# MainBoardV1.net
KiCad netlist of a schematic drawn in EAGLE
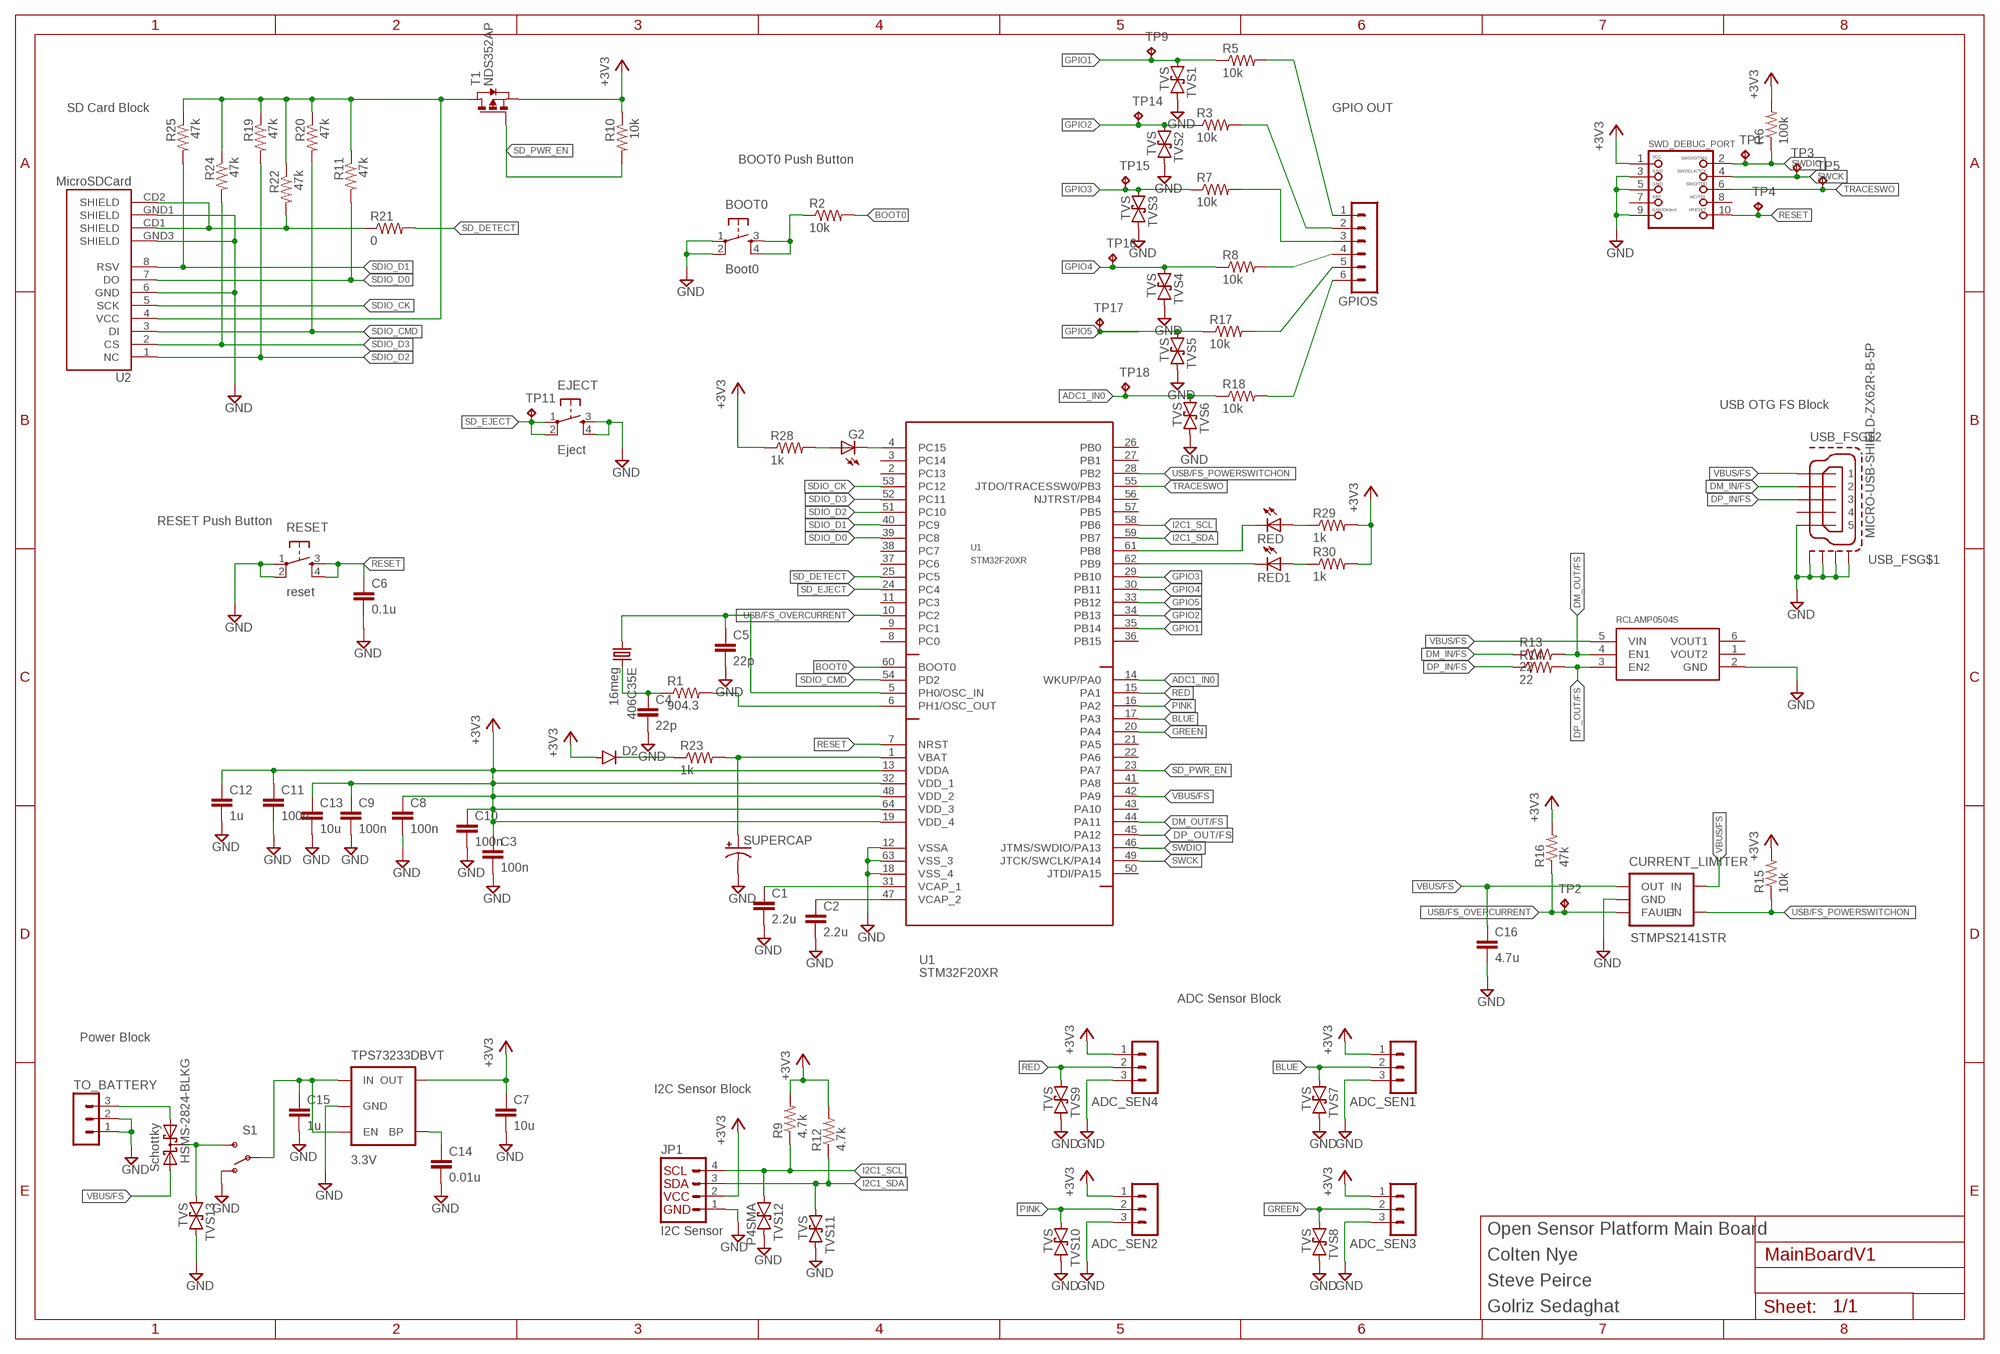
[diagram p0: schematic, sheet 1]

(export (version "E")
  (design (tool "Eeschema 10.0.6"))
  (components
    (comp (ref "406C35E")
      (value "16meg")
      (footprint "eagle-import:CTS406")
      (libsource (lib "eagle-import") (part "CRYSTALCTS406"))
    )
    (comp (ref "ADC_SEN1")
      (value "MA03-1")
      (footprint "eagle-import:MA03-1")
      (libsource (lib "eagle-import") (part "MA03-1"))
    )
    (comp (ref "ADC_SEN2")
      (value "MA03-1")
      (footprint "eagle-import:MA03-1")
      (libsource (lib "eagle-import") (part "MA03-1"))
    )
    (comp (ref "ADC_SEN3")
      (value "MA03-1")
      (footprint "eagle-import:MA03-1")
      (libsource (lib "eagle-import") (part "MA03-1"))
    )
    (comp (ref "ADC_SEN4")
      (value "MA03-1")
      (footprint "eagle-import:MA03-1")
      (libsource (lib "eagle-import") (part "MA03-1"))
    )
    (comp (ref "BOOT0")
      (value "Boot0")
      (footprint "eagle-import:TACTILE-SWITCH-SMD")
      (libsource (lib "eagle-import") (part "TAC_SWITCHSMD"))
    )
    (comp (ref "C1")
      (value "2.2u")
      (footprint "eagle-import:C0805")
      (libsource (lib "eagle-import") (part "C-EUC0805"))
    )
    (comp (ref "C2")
      (value "2.2u")
      (footprint "eagle-import:C0805")
      (libsource (lib "eagle-import") (part "C-EUC0805"))
    )
    (comp (ref "C3")
      (value "100n")
      (footprint "eagle-import:C0805")
      (libsource (lib "eagle-import") (part "C-EUC0805"))
    )
    (comp (ref "C4")
      (value "22p")
      (footprint "eagle-import:C0805")
      (libsource (lib "eagle-import") (part "C-EUC0805"))
    )
    (comp (ref "C5")
      (value "22p")
      (footprint "eagle-import:C0805")
      (libsource (lib "eagle-import") (part "C-EUC0805"))
    )
    (comp (ref "C6")
      (value "0.1u")
      (footprint "eagle-import:C0805")
      (libsource (lib "eagle-import") (part "C-EUC0805"))
    )
    (comp (ref "C7")
      (value "10u")
      (footprint "eagle-import:C0805")
      (libsource (lib "eagle-import") (part "C-EUC0805"))
    )
    (comp (ref "C8")
      (value "100n")
      (footprint "eagle-import:C0805")
      (libsource (lib "eagle-import") (part "C-EUC0805"))
    )
    (comp (ref "C9")
      (value "100n")
      (footprint "eagle-import:C0805")
      (libsource (lib "eagle-import") (part "C-EUC0805"))
    )
    (comp (ref "C10")
      (value "100n")
      (footprint "eagle-import:C0805")
      (libsource (lib "eagle-import") (part "C-EUC0805"))
    )
    (comp (ref "C11")
      (value "100n")
      (footprint "eagle-import:C0805")
      (libsource (lib "eagle-import") (part "C-EUC0805"))
    )
    (comp (ref "C12")
      (value "1u")
      (footprint "eagle-import:C0805")
      (libsource (lib "eagle-import") (part "C-EUC0805"))
    )
    (comp (ref "C13")
      (value "10u")
      (footprint "eagle-import:C0805")
      (libsource (lib "eagle-import") (part "C-EUC0805"))
    )
    (comp (ref "C14")
      (value "0.01u")
      (footprint "eagle-import:C0805")
      (libsource (lib "eagle-import") (part "C-EUC0805"))
    )
    (comp (ref "C15")
      (value "1u")
      (footprint "eagle-import:C0805")
      (libsource (lib "eagle-import") (part "C-EUC0805"))
    )
    (comp (ref "C16")
      (value "4.7u")
      (footprint "eagle-import:C0805")
      (libsource (lib "eagle-import") (part "C-EUC0805"))
    )
    (comp (ref "CURRENT_LIMITER")
      (value "STMPS2141STR")
      (footprint "eagle-import:SOT23-5")
      (libsource (lib "eagle-import") (part "V_REG_NCP1400SOT23-5"))
    )
    (comp (ref "D2")
      (value "DIODESMA")
      (footprint "eagle-import:SMA-DIODE")
      (libsource (lib "eagle-import") (part "DIODESMA"))
    )
    (comp (ref "EJECT")
      (value "Eject")
      (footprint "eagle-import:TACTILE-SWITCH-SMD")
      (libsource (lib "eagle-import") (part "TAC_SWITCHSMD"))
    )
    (comp (ref "G2")
      (value "LEDSML0805")
      (footprint "eagle-import:SML0805")
      (libsource (lib "eagle-import") (part "LEDSML0805"))
    )
    (comp (ref "GPIOS")
      (value "MA06-1")
      (footprint "eagle-import:MA06-1")
      (libsource (lib "eagle-import") (part "MA06-1"))
    )
    (comp (ref "HSMS-2824-BLKG")
      (value "Schottky")
      (footprint "eagle-import:SOT23")
      (libsource (lib "eagle-import") (part "BAS70-05"))
    )
    (comp (ref "JP1")
      (value "I2C Sensor")
      (footprint "eagle-import:1X04")
      (libsource (lib "eagle-import") (part "I2C_STANDARD"))
    )
    (comp (ref "R1")
      (value "904.3")
      (footprint "eagle-import:R0805")
      (libsource (lib "eagle-import") (part "R-US_R0805"))
    )
    (comp (ref "R2")
      (value "10k")
      (footprint "eagle-import:R0805")
      (libsource (lib "eagle-import") (part "R-US_R0805"))
    )
    (comp (ref "R3")
      (value "10k")
      (footprint "eagle-import:R0805")
      (libsource (lib "eagle-import") (part "R-US_R0805"))
    )
    (comp (ref "R5")
      (value "10k")
      (footprint "eagle-import:R0805")
      (libsource (lib "eagle-import") (part "R-US_R0805"))
    )
    (comp (ref "R6")
      (value "100k")
      (footprint "eagle-import:R0805")
      (libsource (lib "eagle-import") (part "R-US_R0805"))
    )
    (comp (ref "R7")
      (value "10k")
      (footprint "eagle-import:R0805")
      (libsource (lib "eagle-import") (part "R-US_R0805"))
    )
    (comp (ref "R8")
      (value "10k")
      (footprint "eagle-import:R0805")
      (libsource (lib "eagle-import") (part "R-US_R0805"))
    )
    (comp (ref "R9")
      (value "4.7k")
      (footprint "eagle-import:R0805")
      (libsource (lib "eagle-import") (part "R-US_R0805"))
    )
    (comp (ref "R10")
      (value "10k")
      (footprint "eagle-import:R0805")
      (libsource (lib "eagle-import") (part "R-US_R0805"))
    )
    (comp (ref "R11")
      (value "47k")
      (footprint "eagle-import:R0805")
      (libsource (lib "eagle-import") (part "R-US_R0805"))
    )
    (comp (ref "R12")
      (value "4.7k")
      (footprint "eagle-import:R0805")
      (libsource (lib "eagle-import") (part "R-US_R0805"))
    )
    (comp (ref "R13")
      (value "22")
      (footprint "eagle-import:R0805")
      (libsource (lib "eagle-import") (part "R-US_R0805"))
    )
    (comp (ref "R14")
      (value "22")
      (footprint "eagle-import:R0805")
      (libsource (lib "eagle-import") (part "R-US_R0805"))
    )
    (comp (ref "R15")
      (value "10k")
      (footprint "eagle-import:R0805")
      (libsource (lib "eagle-import") (part "R-US_R0805"))
    )
    (comp (ref "R16")
      (value "47k")
      (footprint "eagle-import:R0805")
      (libsource (lib "eagle-import") (part "R-US_R0805"))
    )
    (comp (ref "R17")
      (value "10k")
      (footprint "eagle-import:R0805")
      (libsource (lib "eagle-import") (part "R-US_R0805"))
    )
    (comp (ref "R18")
      (value "10k")
      (footprint "eagle-import:R0805")
      (libsource (lib "eagle-import") (part "R-US_R0805"))
    )
    (comp (ref "R19")
      (value "47k")
      (footprint "eagle-import:R0805")
      (libsource (lib "eagle-import") (part "R-US_R0805"))
    )
    (comp (ref "R20")
      (value "47k")
      (footprint "eagle-import:R0805")
      (libsource (lib "eagle-import") (part "R-US_R0805"))
    )
    (comp (ref "R21")
      (value "0")
      (footprint "eagle-import:R0805")
      (libsource (lib "eagle-import") (part "R-US_R0805"))
    )
    (comp (ref "R22")
      (value "47k")
      (footprint "eagle-import:R0805")
      (libsource (lib "eagle-import") (part "R-US_R0805"))
    )
    (comp (ref "R23")
      (value "1k")
      (footprint "eagle-import:R0805")
      (libsource (lib "eagle-import") (part "R-US_R0805"))
    )
    (comp (ref "R24")
      (value "47k")
      (footprint "eagle-import:R0805")
      (libsource (lib "eagle-import") (part "R-US_R0805"))
    )
    (comp (ref "R25")
      (value "47k")
      (footprint "eagle-import:R0805")
      (libsource (lib "eagle-import") (part "R-US_R0805"))
    )
    (comp (ref "R28")
      (value "1k")
      (footprint "eagle-import:R0805")
      (libsource (lib "eagle-import") (part "R-US_R0805"))
    )
    (comp (ref "R29")
      (value "1k")
      (footprint "eagle-import:R0805")
      (libsource (lib "eagle-import") (part "R-US_R0805"))
    )
    (comp (ref "R30")
      (value "1k")
      (footprint "eagle-import:R0805")
      (libsource (lib "eagle-import") (part "R-US_R0805"))
    )
    (comp (ref "RCLAMP0504S")
      (value "VREG_SOT23-6_DUALAP7312")
      (footprint "eagle-import:SOT23-6")
      (libsource (lib "eagle-import") (part "VREG_SOT23-6_DUALAP7312"))
    )
    (comp (ref "RED")
      (value "LEDSML0805")
      (footprint "eagle-import:SML0805")
      (libsource (lib "eagle-import") (part "LEDSML0805"))
    )
    (comp (ref "RED1")
      (value "LEDSML0805")
      (footprint "eagle-import:SML0805")
      (libsource (lib "eagle-import") (part "LEDSML0805"))
    )
    (comp (ref "RESET")
      (value "reset")
      (footprint "eagle-import:TACTILE-SWITCH-SMD")
      (libsource (lib "eagle-import") (part "TAC_SWITCHSMD"))
    )
    (comp (ref "S1")
      (value "SWITCH-SPDTSMD")
      (footprint "eagle-import:AYZ0202")
      (libsource (lib "eagle-import") (part "SWITCH-SPDTSMD"))
    )
    (comp (ref "SUPERCAP")
      (value "SUPERCAP")
      (footprint "eagle-import:414-VA5R")
      (libsource (lib "eagle-import") (part "SUPERCAP"))
    )
    (comp (ref "SWD_DEBUG_PORT")
      (value "JTAG-CORTEXM3")
      (footprint "eagle-import:2X05_1.27MM_SMT")
      (libsource (lib "eagle-import") (part "JTAG-CORTEXM3"))
    )
    (comp (ref "T1")
      (value "NDS352AP")
      (footprint "eagle-import:SOT-23")
      (libsource (lib "eagle-import") (part "PMOSSOT23"))
    )
    (comp (ref "TO_BATTERY")
      (value "MA03-1")
      (footprint "eagle-import:MA03-1")
      (libsource (lib "eagle-import") (part "MA03-1"))
    )
    (comp (ref "TP1")
      (value "TPB1,27")
      (footprint "eagle-import:B1,27")
      (libsource (lib "eagle-import") (part "TPB1,27"))
    )
    (comp (ref "TP2")
      (value "TPB1,27")
      (footprint "eagle-import:B1,27")
      (libsource (lib "eagle-import") (part "TPB1,27"))
    )
    (comp (ref "TP3")
      (value "TPB1,27")
      (footprint "eagle-import:B1,27")
      (libsource (lib "eagle-import") (part "TPB1,27"))
    )
    (comp (ref "TP4")
      (value "TPB1,27")
      (footprint "eagle-import:B1,27")
      (libsource (lib "eagle-import") (part "TPB1,27"))
    )
    (comp (ref "TP5")
      (value "TPB1,27")
      (footprint "eagle-import:B1,27")
      (libsource (lib "eagle-import") (part "TPB1,27"))
    )
    (comp (ref "TP9")
      (value "TPB1,27")
      (footprint "eagle-import:B1,27")
      (libsource (lib "eagle-import") (part "TPB1,27"))
    )
    (comp (ref "TP11")
      (value "TPB1,27")
      (footprint "eagle-import:B1,27")
      (libsource (lib "eagle-import") (part "TPB1,27"))
    )
    (comp (ref "TP14")
      (value "TPB1,27")
      (footprint "eagle-import:B1,27")
      (libsource (lib "eagle-import") (part "TPB1,27"))
    )
    (comp (ref "TP15")
      (value "TPB1,27")
      (footprint "eagle-import:B1,27")
      (libsource (lib "eagle-import") (part "TPB1,27"))
    )
    (comp (ref "TP16")
      (value "TPB1,27")
      (footprint "eagle-import:B1,27")
      (libsource (lib "eagle-import") (part "TPB1,27"))
    )
    (comp (ref "TP17")
      (value "TPB1,27")
      (footprint "eagle-import:B1,27")
      (libsource (lib "eagle-import") (part "TPB1,27"))
    )
    (comp (ref "TP18")
      (value "TPB1,27")
      (footprint "eagle-import:B1,27")
      (libsource (lib "eagle-import") (part "TPB1,27"))
    )
    (comp (ref "TPS73233DBVT")
      (value "3.3V")
      (footprint "eagle-import:SOT23-5")
      (libsource (lib "eagle-import") (part "V_REG_MIC52053.3V"))
    )
    (comp (ref "TVS1")
      (value "TVS")
      (footprint "eagle-import:SMA-DIODE")
      (libsource (lib "eagle-import") (part "TVS"))
    )
    (comp (ref "TVS2")
      (value "TVS")
      (footprint "eagle-import:SMA-DIODE")
      (libsource (lib "eagle-import") (part "TVS"))
    )
    (comp (ref "TVS3")
      (value "TVS")
      (footprint "eagle-import:SMA-DIODE")
      (libsource (lib "eagle-import") (part "TVS"))
    )
    (comp (ref "TVS4")
      (value "TVS")
      (footprint "eagle-import:SMA-DIODE")
      (libsource (lib "eagle-import") (part "TVS"))
    )
    (comp (ref "TVS5")
      (value "TVS")
      (footprint "eagle-import:SMA-DIODE")
      (libsource (lib "eagle-import") (part "TVS"))
    )
    (comp (ref "TVS6")
      (value "TVS")
      (footprint "eagle-import:SMA-DIODE")
      (libsource (lib "eagle-import") (part "TVS"))
    )
    (comp (ref "TVS7")
      (value "TVS")
      (footprint "eagle-import:SMA-DIODE")
      (libsource (lib "eagle-import") (part "TVS"))
    )
    (comp (ref "TVS8")
      (value "TVS")
      (footprint "eagle-import:SMA-DIODE")
      (libsource (lib "eagle-import") (part "TVS"))
    )
    (comp (ref "TVS9")
      (value "TVS")
      (footprint "eagle-import:SMA-DIODE")
      (libsource (lib "eagle-import") (part "TVS"))
    )
    (comp (ref "TVS10")
      (value "TVS")
      (footprint "eagle-import:SMA-DIODE")
      (libsource (lib "eagle-import") (part "TVS"))
    )
    (comp (ref "TVS11")
      (value "TVS")
      (footprint "eagle-import:SMA-DIODE")
      (libsource (lib "eagle-import") (part "TVS"))
    )
    (comp (ref "TVS12")
      (value "P4SMA")
      (footprint "eagle-import:SMA-DIODE")
      (libsource (lib "eagle-import") (part "TVS"))
    )
    (comp (ref "TVS13")
      (value "TVS")
      (footprint "eagle-import:SMA-DIODE")
      (libsource (lib "eagle-import") (part "TVS"))
    )
    (comp (ref "U1")
      (value "STM32F20XR")
      (footprint "eagle-import:LQFP64")
      (libsource (lib "eagle-import") (part "STM32F20XR"))
    )
    (comp (ref "U2")
      (value "MicroSDCard")
      (footprint "eagle-import:MICRO-SD-SOCKET-PP")
      (libsource (lib "eagle-import") (part "USD-SOCKETNEW"))
    )
    (comp (ref "USB_FS")
      (value "MICRO-USB-SHIELD-ZX62R-B-5P")
      (footprint "eagle-import:ZX62R-B-5P")
      (libsource (lib "eagle-import") (part "MICRO-USB-SHIELD-ZX62R-B-5P"))
    )
  )
  (nets
    (net (code "1") (name "+3V3") (class "Default")
      (node (ref "ADC_SEN1") (pin "1") (pinfunction "1_1") (pintype "passive"))
      (node (ref "ADC_SEN2") (pin "1") (pinfunction "1_1") (pintype "passive"))
      (node (ref "ADC_SEN3") (pin "1") (pinfunction "1_1") (pintype "passive"))
      (node (ref "ADC_SEN4") (pin "1") (pinfunction "1_1") (pintype "passive"))
      (node (ref "C10") (pin "1") (pinfunction "1_1") (pintype "passive"))
      (node (ref "C11") (pin "1") (pinfunction "1_1") (pintype "passive"))
      (node (ref "C12") (pin "1") (pinfunction "1_1") (pintype "passive"))
      (node (ref "C13") (pin "1") (pinfunction "1_1") (pintype "passive"))
      (node (ref "C3") (pin "1") (pinfunction "1_1") (pintype "passive"))
      (node (ref "C7") (pin "1") (pinfunction "1_1") (pintype "passive"))
      (node (ref "C8") (pin "1") (pinfunction "1_1") (pintype "passive"))
      (node (ref "C9") (pin "1") (pinfunction "1_1") (pintype "passive"))
      (node (ref "D2") (pin "A") (pinfunction "A_A") (pintype "passive"))
      (node (ref "JP1") (pin "2") (pinfunction "2_2") (pintype "passive"))
      (node (ref "R10") (pin "1") (pinfunction "1_1") (pintype "passive"))
      (node (ref "R12") (pin "2") (pinfunction "2_2") (pintype "passive"))
      (node (ref "R15") (pin "2") (pinfunction "2_2") (pintype "passive"))
      (node (ref "R16") (pin "2") (pinfunction "2_2") (pintype "passive"))
      (node (ref "R28") (pin "1") (pinfunction "1_1") (pintype "passive"))
      (node (ref "R29") (pin "2") (pinfunction "2_2") (pintype "passive"))
      (node (ref "R30") (pin "2") (pinfunction "2_2") (pintype "passive"))
      (node (ref "R6") (pin "2") (pinfunction "2_2") (pintype "passive"))
      (node (ref "R9") (pin "2") (pinfunction "2_2") (pintype "passive"))
      (node (ref "SWD_DEBUG_PORT") (pin "1") (pinfunction "1_1") (pintype "passive"))
      (node (ref "T1") (pin "2") (pinfunction "S_2") (pintype "passive"))
      (node (ref "TPS73233DBVT") (pin "5") (pinfunction "OUT_5") (pintype "passive"))
      (node (ref "U1") (pin "13") (pinfunction "VDDA_13") (pintype "power_in"))
      (node (ref "U1") (pin "19") (pinfunction "VDD_4_19") (pintype "power_in"))
      (node (ref "U1") (pin "32") (pinfunction "VDD_1_32") (pintype "power_in"))
      (node (ref "U1") (pin "48") (pinfunction "VDD_2_48") (pintype "power_in"))
      (node (ref "U1") (pin "64") (pinfunction "VDD_3_64") (pintype "power_in"))
    )
    (net (code "2") (name "ADC1_IN0") (class "Default")
      (node (ref "R18") (pin "1") (pinfunction "1_1") (pintype "passive"))
      (node (ref "TP18") (pin "TP") (pinfunction "TP_TP") (pintype "input"))
      (node (ref "TVS6") (pin "A") (pinfunction "1_A") (pintype "passive"))
      (node (ref "U1") (pin "14") (pinfunction "WKUP/PA0_14") (pintype "bidirectional"))
    )
    (net (code "3") (name "BLUE") (class "Default")
      (node (ref "ADC_SEN1") (pin "2") (pinfunction "2_2") (pintype "passive"))
      (node (ref "TVS7") (pin "A") (pinfunction "1_A") (pintype "passive"))
      (node (ref "U1") (pin "17") (pinfunction "PA3_17") (pintype "bidirectional"))
    )
    (net (code "4") (name "BOOT0") (class "Default")
      (node (ref "R2") (pin "2") (pinfunction "2_2") (pintype "passive"))
      (node (ref "U1") (pin "60") (pinfunction "BOOT0_60") (pintype "bidirectional"))
    )
    (net (code "5") (name "DM_IN{slash}FS") (class "Default")
      (node (ref "R13") (pin "1") (pinfunction "1_1") (pintype "passive"))
      (node (ref "USB_FS") (pin "2") (pinfunction "2_2") (pintype "input"))
    )
    (net (code "6") (name "DM_OUT{slash}FS") (class "Default")
      (node (ref "R13") (pin "2") (pinfunction "2_2") (pintype "passive"))
      (node (ref "RCLAMP0504S") (pin "4") (pinfunction "EN1_4") (pintype "bidirectional"))
      (node (ref "U1") (pin "44") (pinfunction "PA11_44") (pintype "bidirectional"))
    )
    (net (code "7") (name "DP_IN{slash}FS") (class "Default")
      (node (ref "R14") (pin "1") (pinfunction "1_1") (pintype "passive"))
      (node (ref "USB_FS") (pin "3") (pinfunction "3_3") (pintype "input"))
    )
    (net (code "8") (name "DP_OUT{slash}FS") (class "Default")
      (node (ref "R14") (pin "2") (pinfunction "2_2") (pintype "passive"))
      (node (ref "RCLAMP0504S") (pin "3") (pinfunction "EN2_3") (pintype "bidirectional"))
      (node (ref "U1") (pin "45") (pinfunction "PA12_45") (pintype "bidirectional"))
    )
    (net (code "9") (name "GND") (class "Default")
      (node (ref "ADC_SEN1") (pin "3") (pinfunction "3_3") (pintype "passive"))
      (node (ref "ADC_SEN2") (pin "3") (pinfunction "3_3") (pintype "passive"))
      (node (ref "ADC_SEN3") (pin "3") (pinfunction "3_3") (pintype "passive"))
      (node (ref "ADC_SEN4") (pin "3") (pinfunction "3_3") (pintype "passive"))
      (node (ref "BOOT0") (pin "1") (pinfunction "1_1") (pintype "passive"))
      (node (ref "BOOT0") (pin "2") (pinfunction "2_2") (pintype "passive"))
      (node (ref "C1") (pin "2") (pinfunction "2_2") (pintype "passive"))
      (node (ref "C10") (pin "2") (pinfunction "2_2") (pintype "passive"))
      (node (ref "C11") (pin "2") (pinfunction "2_2") (pintype "passive"))
      (node (ref "C12") (pin "2") (pinfunction "2_2") (pintype "passive"))
      (node (ref "C13") (pin "2") (pinfunction "2_2") (pintype "passive"))
      (node (ref "C14") (pin "2") (pinfunction "2_2") (pintype "passive"))
      (node (ref "C15") (pin "2") (pinfunction "2_2") (pintype "passive"))
      (node (ref "C16") (pin "2") (pinfunction "2_2") (pintype "passive"))
      (node (ref "C2") (pin "2") (pinfunction "2_2") (pintype "passive"))
      (node (ref "C3") (pin "2") (pinfunction "2_2") (pintype "passive"))
      (node (ref "C4") (pin "2") (pinfunction "2_2") (pintype "passive"))
      (node (ref "C5") (pin "2") (pinfunction "2_2") (pintype "passive"))
      (node (ref "C6") (pin "2") (pinfunction "2_2") (pintype "passive"))
      (node (ref "C7") (pin "2") (pinfunction "2_2") (pintype "passive"))
      (node (ref "C8") (pin "2") (pinfunction "2_2") (pintype "passive"))
      (node (ref "C9") (pin "2") (pinfunction "2_2") (pintype "passive"))
      (node (ref "CURRENT_LIMITER") (pin "4") (pinfunction "GND_4") (pintype "input"))
      (node (ref "EJECT") (pin "3") (pinfunction "3_3") (pintype "passive"))
      (node (ref "EJECT") (pin "4") (pinfunction "4_4") (pintype "passive"))
      (node (ref "JP1") (pin "1") (pinfunction "1_1") (pintype "passive"))
      (node (ref "RCLAMP0504S") (pin "2") (pinfunction "GND_2") (pintype "bidirectional"))
      (node (ref "RESET") (pin "1") (pinfunction "1_1") (pintype "passive"))
      (node (ref "RESET") (pin "2") (pinfunction "2_2") (pintype "passive"))
      (node (ref "S1") (pin "1") (pinfunction "O_1") (pintype "passive"))
      (node (ref "SUPERCAP") (pin "-") (pinfunction "-_-") (pintype "passive"))
      (node (ref "SWD_DEBUG_PORT") (pin "3") (pinfunction "3_3") (pintype "passive"))
      (node (ref "SWD_DEBUG_PORT") (pin "5") (pinfunction "5_5") (pintype "passive"))
      (node (ref "SWD_DEBUG_PORT") (pin "9") (pinfunction "9_9") (pintype "passive"))
      (node (ref "TO_BATTERY") (pin "1") (pinfunction "1_1") (pintype "passive"))
      (node (ref "TO_BATTERY") (pin "2") (pinfunction "2_2") (pintype "passive"))
      (node (ref "TPS73233DBVT") (pin "2") (pinfunction "GND_2") (pintype "input"))
      (node (ref "TVS1") (pin "C") (pinfunction "2_C") (pintype "passive"))
      (node (ref "TVS10") (pin "C") (pinfunction "2_C") (pintype "passive"))
      (node (ref "TVS11") (pin "C") (pinfunction "2_C") (pintype "passive"))
      (node (ref "TVS12") (pin "C") (pinfunction "2_C") (pintype "passive"))
      (node (ref "TVS13") (pin "C") (pinfunction "2_C") (pintype "passive"))
      (node (ref "TVS2") (pin "C") (pinfunction "2_C") (pintype "passive"))
      (node (ref "TVS3") (pin "C") (pinfunction "2_C") (pintype "passive"))
      (node (ref "TVS4") (pin "C") (pinfunction "2_C") (pintype "passive"))
      (node (ref "TVS5") (pin "C") (pinfunction "2_C") (pintype "passive"))
      (node (ref "TVS6") (pin "C") (pinfunction "2_C") (pintype "passive"))
      (node (ref "TVS7") (pin "C") (pinfunction "2_C") (pintype "passive"))
      (node (ref "TVS8") (pin "C") (pinfunction "2_C") (pintype "passive"))
      (node (ref "TVS9") (pin "C") (pinfunction "2_C") (pintype "passive"))
      (node (ref "U1") (pin "12") (pinfunction "VSSA_12") (pintype "power_in"))
      (node (ref "U1") (pin "18") (pinfunction "VSS_4_18") (pintype "power_in"))
      (node (ref "U1") (pin "63") (pinfunction "VSS_3_63") (pintype "power_in"))
      (node (ref "U2") (pin "6") (pinfunction "GND_6") (pintype "bidirectional"))
      (node (ref "U2") (pin "GND1") (pinfunction "SHIELD_GND1") (pintype "bidirectional"))
      (node (ref "U2") (pin "GND3") (pinfunction "SHIELD_GND3") (pintype "bidirectional"))
      (node (ref "USB_FS") (pin "5") (pinfunction "5_5") (pintype "input"))
      (node (ref "USB_FS") (pin "M1") (pinfunction "S1_M1") (pintype "passive"))
      (node (ref "USB_FS") (pin "M2") (pinfunction "S2_M2") (pintype "passive"))
      (node (ref "USB_FS") (pin "M3") (pinfunction "S3_M3") (pintype "passive"))
      (node (ref "USB_FS") (pin "M4") (pinfunction "S4_M4") (pintype "passive"))
    )
    (net (code "10") (name "GPIO1") (class "Default")
      (node (ref "R5") (pin "1") (pinfunction "1_1") (pintype "passive"))
      (node (ref "TP9") (pin "TP") (pinfunction "TP_TP") (pintype "input"))
      (node (ref "TVS1") (pin "A") (pinfunction "1_A") (pintype "passive"))
      (node (ref "U1") (pin "35") (pinfunction "PB14_35") (pintype "bidirectional"))
    )
    (net (code "11") (name "GPIO2") (class "Default")
      (node (ref "R3") (pin "1") (pinfunction "1_1") (pintype "passive"))
      (node (ref "TP14") (pin "TP") (pinfunction "TP_TP") (pintype "input"))
      (node (ref "TVS2") (pin "A") (pinfunction "1_A") (pintype "passive"))
      (node (ref "U1") (pin "34") (pinfunction "PB13_34") (pintype "bidirectional"))
    )
    (net (code "12") (name "GPIO3") (class "Default")
      (node (ref "R7") (pin "1") (pinfunction "1_1") (pintype "passive"))
      (node (ref "TP15") (pin "TP") (pinfunction "TP_TP") (pintype "input"))
      (node (ref "TVS3") (pin "A") (pinfunction "1_A") (pintype "passive"))
      (node (ref "U1") (pin "29") (pinfunction "PB10_29") (pintype "bidirectional"))
    )
    (net (code "13") (name "GPIO4") (class "Default")
      (node (ref "R8") (pin "1") (pinfunction "1_1") (pintype "passive"))
      (node (ref "TP16") (pin "TP") (pinfunction "TP_TP") (pintype "input"))
      (node (ref "TVS4") (pin "A") (pinfunction "1_A") (pintype "passive"))
      (node (ref "U1") (pin "30") (pinfunction "PB11_30") (pintype "bidirectional"))
    )
    (net (code "14") (name "GPIO5") (class "Default")
      (node (ref "R17") (pin "1") (pinfunction "1_1") (pintype "passive"))
      (node (ref "TP17") (pin "TP") (pinfunction "TP_TP") (pintype "input"))
      (node (ref "TVS5") (pin "A") (pinfunction "1_A") (pintype "passive"))
      (node (ref "U1") (pin "33") (pinfunction "PB12_33") (pintype "bidirectional"))
    )
    (net (code "15") (name "GREEN") (class "Default")
      (node (ref "ADC_SEN3") (pin "2") (pinfunction "2_2") (pintype "passive"))
      (node (ref "TVS8") (pin "A") (pinfunction "1_A") (pintype "passive"))
      (node (ref "U1") (pin "20") (pinfunction "PA4_20") (pintype "bidirectional"))
    )
    (net (code "16") (name "I2C1_SCL") (class "Default")
      (node (ref "JP1") (pin "4") (pinfunction "4_4") (pintype "passive"))
      (node (ref "R9") (pin "1") (pinfunction "1_1") (pintype "passive"))
      (node (ref "TVS12") (pin "A") (pinfunction "1_A") (pintype "passive"))
      (node (ref "U1") (pin "58") (pinfunction "PB6_58") (pintype "bidirectional"))
    )
    (net (code "17") (name "I2C1_SDA") (class "Default")
      (node (ref "JP1") (pin "3") (pinfunction "3_3") (pintype "passive"))
      (node (ref "R12") (pin "1") (pinfunction "1_1") (pintype "passive"))
      (node (ref "TVS11") (pin "A") (pinfunction "1_A") (pintype "passive"))
      (node (ref "U1") (pin "59") (pinfunction "PB7_59") (pintype "bidirectional"))
    )
    (net (code "18") (name "Net-(406C35E-2)") (class "Default")
      (node (ref "406C35E") (pin "3") (pinfunction "2_3") (pintype "passive"))
      (node (ref "C4") (pin "1") (pinfunction "1_1") (pintype "passive"))
      (node (ref "R1") (pin "1") (pinfunction "1_1") (pintype "passive"))
    )
    (net (code "19") (name "Net-(BOOT0-Pad3)") (class "Default")
      (node (ref "BOOT0") (pin "3") (pinfunction "3_3") (pintype "passive"))
      (node (ref "BOOT0") (pin "4") (pinfunction "4_4") (pintype "passive"))
      (node (ref "R2") (pin "1") (pinfunction "1_1") (pintype "passive"))
    )
    (net (code "20") (name "Net-(D2-PadC)") (class "Default")
      (node (ref "D2") (pin "C") (pinfunction "C_C") (pintype "passive"))
      (node (ref "R23") (pin "1") (pinfunction "1_1") (pintype "passive"))
    )
    (net (code "21") (name "Net-(G2-PadA)") (class "Default")
      (node (ref "G2") (pin "A") (pinfunction "A_A") (pintype "passive"))
      (node (ref "R28") (pin "2") (pinfunction "2_2") (pintype "passive"))
    )
    (net (code "22") (name "Net-(GPIOS-Pad1)") (class "Default")
      (node (ref "GPIOS") (pin "1") (pinfunction "1_1") (pintype "passive"))
      (node (ref "R5") (pin "2") (pinfunction "2_2") (pintype "passive"))
    )
    (net (code "23") (name "Net-(GPIOS-Pad2)") (class "Default")
      (node (ref "GPIOS") (pin "2") (pinfunction "2_2") (pintype "passive"))
      (node (ref "R3") (pin "2") (pinfunction "2_2") (pintype "passive"))
    )
    (net (code "24") (name "Net-(GPIOS-Pad3)") (class "Default")
      (node (ref "GPIOS") (pin "3") (pinfunction "3_3") (pintype "passive"))
      (node (ref "R7") (pin "2") (pinfunction "2_2") (pintype "passive"))
    )
    (net (code "25") (name "Net-(GPIOS-Pad4)") (class "Default")
      (node (ref "GPIOS") (pin "4") (pinfunction "4_4") (pintype "passive"))
      (node (ref "R8") (pin "2") (pinfunction "2_2") (pintype "passive"))
    )
    (net (code "26") (name "Net-(GPIOS-Pad5)") (class "Default")
      (node (ref "GPIOS") (pin "5") (pinfunction "5_5") (pintype "passive"))
      (node (ref "R17") (pin "2") (pinfunction "2_2") (pintype "passive"))
    )
    (net (code "27") (name "Net-(GPIOS-Pad6)") (class "Default")
      (node (ref "GPIOS") (pin "6") (pinfunction "6_6") (pintype "passive"))
      (node (ref "R18") (pin "2") (pinfunction "2_2") (pintype "passive"))
    )
    (net (code "28") (name "Net-(HSMS-2824-BLKG-A1)") (class "Default")
      (node (ref "HSMS-2824-BLKG") (pin "1") (pinfunction "A1_1") (pintype "passive"))
      (node (ref "TO_BATTERY") (pin "3") (pinfunction "3_3") (pintype "passive"))
    )
    (net (code "29") (name "Net-(HSMS-2824-BLKG-C)") (class "Default")
      (node (ref "HSMS-2824-BLKG") (pin "3") (pinfunction "C_3") (pintype "passive"))
      (node (ref "S1") (pin "3") (pinfunction "S_3") (pintype "passive"))
      (node (ref "TVS13") (pin "A") (pinfunction "1_A") (pintype "passive"))
    )
    (net (code "30") (name "Net-(R21-Pad1)") (class "Default")
      (node (ref "R21") (pin "1") (pinfunction "1_1") (pintype "passive"))
      (node (ref "R22") (pin "2") (pinfunction "2_2") (pintype "passive"))
      (node (ref "U2") (pin "CD1") (pinfunction "SHIELD_CD1") (pintype "bidirectional"))
      (node (ref "U2") (pin "CD2") (pinfunction "SHIELD_CD2") (pintype "bidirectional"))
    )
    (net (code "31") (name "Net-(R29-Pad1)") (class "Default")
      (node (ref "R29") (pin "1") (pinfunction "1_1") (pintype "passive"))
      (node (ref "RED") (pin "A") (pinfunction "A_A") (pintype "passive"))
    )
    (net (code "32") (name "Net-(R30-Pad1)") (class "Default")
      (node (ref "R30") (pin "1") (pinfunction "1_1") (pintype "passive"))
      (node (ref "RED1") (pin "A") (pinfunction "A_A") (pintype "passive"))
    )
    (net (code "33") (name "Net-(S1-P)") (class "Default")
      (node (ref "C15") (pin "1") (pinfunction "1_1") (pintype "passive"))
      (node (ref "S1") (pin "2") (pinfunction "P_2") (pintype "passive"))
      (node (ref "TPS73233DBVT") (pin "1") (pinfunction "IN_1") (pintype "input"))
      (node (ref "TPS73233DBVT") (pin "3") (pinfunction "EN_3") (pintype "input"))
    )
    (net (code "34") (name "Net-(T1-D)") (class "Default")
      (node (ref "R11") (pin "1") (pinfunction "1_1") (pintype "passive"))
      (node (ref "R19") (pin "1") (pinfunction "1_1") (pintype "passive"))
      (node (ref "R20") (pin "1") (pinfunction "1_1") (pintype "passive"))
      (node (ref "R22") (pin "1") (pinfunction "1_1") (pintype "passive"))
      (node (ref "R24") (pin "1") (pinfunction "1_1") (pintype "passive"))
      (node (ref "R25") (pin "1") (pinfunction "1_1") (pintype "passive"))
      (node (ref "T1") (pin "1") (pinfunction "D_1") (pintype "passive"))
      (node (ref "U2") (pin "4") (pinfunction "VCC_4") (pintype "bidirectional"))
    )
    (net (code "35") (name "Net-(TPS73233DBVT-BP)") (class "Default")
      (node (ref "C14") (pin "1") (pinfunction "1_1") (pintype "passive"))
      (node (ref "TPS73233DBVT") (pin "4") (pinfunction "BP_4") (pintype "input"))
    )
    (net (code "36") (name "Net-(U1-PB8)") (class "Default")
      (node (ref "RED") (pin "C") (pinfunction "C_C") (pintype "passive"))
      (node (ref "U1") (pin "61") (pinfunction "PB8_61") (pintype "bidirectional"))
    )
    (net (code "37") (name "Net-(U1-PB9)") (class "Default")
      (node (ref "RED1") (pin "C") (pinfunction "C_C") (pintype "passive"))
      (node (ref "U1") (pin "62") (pinfunction "PB9_62") (pintype "bidirectional"))
    )
    (net (code "38") (name "Net-(U1-PC15)") (class "Default")
      (node (ref "G2") (pin "C") (pinfunction "C_C") (pintype "passive"))
      (node (ref "U1") (pin "4") (pinfunction "PC15_4") (pintype "bidirectional"))
    )
    (net (code "39") (name "Net-(U1-PH0{slash}OSC_IN)") (class "Default")
      (node (ref "406C35E") (pin "1") (pinfunction "1_1") (pintype "passive"))
      (node (ref "C5") (pin "1") (pinfunction "1_1") (pintype "passive"))
      (node (ref "U1") (pin "5") (pinfunction "PH0/OSC_IN_5") (pintype "bidirectional"))
    )
    (net (code "40") (name "Net-(U1-PH1{slash}OSC_OUT)") (class "Default")
      (node (ref "R1") (pin "2") (pinfunction "2_2") (pintype "passive"))
      (node (ref "U1") (pin "6") (pinfunction "PH1/OSC_OUT_6") (pintype "bidirectional"))
    )
    (net (code "41") (name "Net-(U1-VBAT)") (class "Default")
      (node (ref "R23") (pin "2") (pinfunction "2_2") (pintype "passive"))
      (node (ref "SUPERCAP") (pin "+") (pinfunction "+_+") (pintype "passive"))
      (node (ref "U1") (pin "1") (pinfunction "VBAT_1") (pintype "power_in"))
    )
    (net (code "42") (name "Net-(U1-VCAP_1)") (class "Default")
      (node (ref "C1") (pin "1") (pinfunction "1_1") (pintype "passive"))
      (node (ref "U1") (pin "31") (pinfunction "VCAP_1_31") (pintype "power_in"))
    )
    (net (code "43") (name "Net-(U1-VCAP_2)") (class "Default")
      (node (ref "C2") (pin "1") (pinfunction "1_1") (pintype "passive"))
      (node (ref "U1") (pin "47") (pinfunction "VCAP_2_47") (pintype "power_in"))
    )
    (net (code "44") (name "PINK") (class "Default")
      (node (ref "ADC_SEN2") (pin "2") (pinfunction "2_2") (pintype "passive"))
      (node (ref "TVS10") (pin "A") (pinfunction "1_A") (pintype "passive"))
      (node (ref "U1") (pin "16") (pinfunction "PA2_16") (pintype "bidirectional"))
    )
    (net (code "45") (name "RED") (class "Default")
      (node (ref "ADC_SEN4") (pin "2") (pinfunction "2_2") (pintype "passive"))
      (node (ref "TVS9") (pin "A") (pinfunction "1_A") (pintype "passive"))
      (node (ref "U1") (pin "15") (pinfunction "PA1_15") (pintype "bidirectional"))
    )
    (net (code "46") (name "RESET") (class "Default")
      (node (ref "C6") (pin "1") (pinfunction "1_1") (pintype "passive"))
      (node (ref "RESET") (pin "3") (pinfunction "3_3") (pintype "passive"))
      (node (ref "RESET") (pin "4") (pinfunction "4_4") (pintype "passive"))
      (node (ref "SWD_DEBUG_PORT") (pin "10") (pinfunction "10_10") (pintype "passive"))
      (node (ref "TP4") (pin "TP") (pinfunction "TP_TP") (pintype "input"))
      (node (ref "U1") (pin "7") (pinfunction "NRST_7") (pintype "power_in"))
    )
    (net (code "47") (name "SDIO_CK") (class "Default")
      (node (ref "U1") (pin "53") (pinfunction "PC12_53") (pintype "bidirectional"))
      (node (ref "U2") (pin "5") (pinfunction "SCK_5") (pintype "bidirectional"))
    )
    (net (code "48") (name "SDIO_CMD") (class "Default")
      (node (ref "R20") (pin "2") (pinfunction "2_2") (pintype "passive"))
      (node (ref "U1") (pin "54") (pinfunction "PD2_54") (pintype "bidirectional"))
      (node (ref "U2") (pin "3") (pinfunction "DI_3") (pintype "bidirectional"))
    )
    (net (code "49") (name "SDIO_D0") (class "Default")
      (node (ref "R11") (pin "2") (pinfunction "2_2") (pintype "passive"))
      (node (ref "U1") (pin "39") (pinfunction "PC8_39") (pintype "bidirectional"))
      (node (ref "U2") (pin "7") (pinfunction "DO_7") (pintype "bidirectional"))
    )
    (net (code "50") (name "SDIO_D1") (class "Default")
      (node (ref "R25") (pin "2") (pinfunction "2_2") (pintype "passive"))
      (node (ref "U1") (pin "40") (pinfunction "PC9_40") (pintype "bidirectional"))
      (node (ref "U2") (pin "8") (pinfunction "RSV_8") (pintype "bidirectional"))
    )
    (net (code "51") (name "SDIO_D2") (class "Default")
      (node (ref "R19") (pin "2") (pinfunction "2_2") (pintype "passive"))
      (node (ref "U1") (pin "51") (pinfunction "PC10_51") (pintype "bidirectional"))
      (node (ref "U2") (pin "1") (pinfunction "NC_1") (pintype "bidirectional"))
    )
    (net (code "52") (name "SDIO_D3") (class "Default")
      (node (ref "R24") (pin "2") (pinfunction "2_2") (pintype "passive"))
      (node (ref "U1") (pin "52") (pinfunction "PC11_52") (pintype "bidirectional"))
      (node (ref "U2") (pin "2") (pinfunction "CS_2") (pintype "bidirectional"))
    )
    (net (code "53") (name "SD_DETECT") (class "Default")
      (node (ref "R21") (pin "2") (pinfunction "2_2") (pintype "passive"))
      (node (ref "U1") (pin "25") (pinfunction "PC5_25") (pintype "bidirectional"))
    )
    (net (code "54") (name "SD_EJECT") (class "Default")
      (node (ref "EJECT") (pin "1") (pinfunction "1_1") (pintype "passive"))
      (node (ref "EJECT") (pin "2") (pinfunction "2_2") (pintype "passive"))
      (node (ref "TP11") (pin "TP") (pinfunction "TP_TP") (pintype "input"))
      (node (ref "U1") (pin "24") (pinfunction "PC4_24") (pintype "bidirectional"))
    )
    (net (code "55") (name "SD_PWR_EN") (class "Default")
      (node (ref "R10") (pin "2") (pinfunction "2_2") (pintype "passive"))
      (node (ref "T1") (pin "3") (pinfunction "G_3") (pintype "passive"))
      (node (ref "U1") (pin "23") (pinfunction "PA7_23") (pintype "bidirectional"))
    )
    (net (code "56") (name "SWCK") (class "Default")
      (node (ref "SWD_DEBUG_PORT") (pin "4") (pinfunction "4_4") (pintype "passive"))
      (node (ref "TP3") (pin "TP") (pinfunction "TP_TP") (pintype "input"))
      (node (ref "U1") (pin "49") (pinfunction "JTCK/SWCLK/PA14_49") (pintype "bidirectional"))
    )
    (net (code "57") (name "SWDIO") (class "Default")
      (node (ref "R6") (pin "1") (pinfunction "1_1") (pintype "passive"))
      (node (ref "SWD_DEBUG_PORT") (pin "2") (pinfunction "2_2") (pintype "passive"))
      (node (ref "TP1") (pin "TP") (pinfunction "TP_TP") (pintype "input"))
      (node (ref "U1") (pin "46") (pinfunction "JTMS/SWDIO/PA13_46") (pintype "bidirectional"))
    )
    (net (code "58") (name "TRACESWO") (class "Default")
      (node (ref "SWD_DEBUG_PORT") (pin "6") (pinfunction "6_6") (pintype "passive"))
      (node (ref "TP5") (pin "TP") (pinfunction "TP_TP") (pintype "input"))
      (node (ref "U1") (pin "55") (pinfunction "JTDO/TRACESSW0/PB3_55") (pintype "bidirectional"))
    )
    (net (code "59") (name "USB{slash}FS_OVERCURRENT") (class "Default")
      (node (ref "CURRENT_LIMITER") (pin "3") (pinfunction "FAULT_3") (pintype "input"))
      (node (ref "R16") (pin "1") (pinfunction "1_1") (pintype "passive"))
      (node (ref "TP2") (pin "TP") (pinfunction "TP_TP") (pintype "input"))
      (node (ref "U1") (pin "10") (pinfunction "PC2_10") (pintype "bidirectional"))
    )
    (net (code "60") (name "USB{slash}FS_POWERSWITCHON") (class "Default")
      (node (ref "CURRENT_LIMITER") (pin "1") (pinfunction "EN_1") (pintype "input"))
      (node (ref "R15") (pin "1") (pinfunction "1_1") (pintype "passive"))
      (node (ref "U1") (pin "28") (pinfunction "PB2_28") (pintype "bidirectional"))
    )
    (net (code "61") (name "VBUS{slash}FS") (class "Default")
      (node (ref "C16") (pin "1") (pinfunction "1_1") (pintype "passive"))
      (node (ref "CURRENT_LIMITER") (pin "2") (pinfunction "OUT_2") (pintype "passive"))
      (node (ref "CURRENT_LIMITER") (pin "5") (pinfunction "IN_5") (pintype "input"))
      (node (ref "HSMS-2824-BLKG") (pin "2") (pinfunction "A2_2") (pintype "passive"))
      (node (ref "RCLAMP0504S") (pin "5") (pinfunction "VIN_5") (pintype "bidirectional"))
      (node (ref "U1") (pin "42") (pinfunction "PA9_42") (pintype "bidirectional"))
      (node (ref "USB_FS") (pin "1") (pinfunction "1_1") (pintype "input"))
    )
    (net (code "62") (name "unconnected-(RCLAMP0504S-VOUT1-Pad6)") (class "Default")
      (node (ref "RCLAMP0504S") (pin "6") (pinfunction "VOUT1_6") (pintype "bidirectional"))
    )
    (net (code "63") (name "unconnected-(RCLAMP0504S-VOUT2-Pad1)") (class "Default")
      (node (ref "RCLAMP0504S") (pin "1") (pinfunction "VOUT2_1") (pintype "bidirectional"))
    )
    (net (code "64") (name "unconnected-(SWD_DEBUG_PORT-Pad7)") (class "Default")
      (node (ref "SWD_DEBUG_PORT") (pin "7") (pinfunction "7_7") (pintype "passive"))
    )
    (net (code "65") (name "unconnected-(SWD_DEBUG_PORT-Pad8)") (class "Default")
      (node (ref "SWD_DEBUG_PORT") (pin "8") (pinfunction "8_8") (pintype "passive"))
    )
    (net (code "66") (name "unconnected-(U1-JTDI{slash}PA15-Pad50)") (class "Default")
      (node (ref "U1") (pin "50") (pinfunction "JTDI/PA15_50") (pintype "bidirectional"))
    )
    (net (code "67") (name "unconnected-(U1-NJTRST{slash}PB4-Pad56)") (class "Default")
      (node (ref "U1") (pin "56") (pinfunction "NJTRST/PB4_56") (pintype "bidirectional"))
    )
    (net (code "68") (name "unconnected-(U1-PA5-Pad21)") (class "Default")
      (node (ref "U1") (pin "21") (pinfunction "PA5_21") (pintype "bidirectional"))
    )
    (net (code "69") (name "unconnected-(U1-PA6-Pad22)") (class "Default")
      (node (ref "U1") (pin "22") (pinfunction "PA6_22") (pintype "bidirectional"))
    )
    (net (code "70") (name "unconnected-(U1-PA8-Pad41)") (class "Default")
      (node (ref "U1") (pin "41") (pinfunction "PA8_41") (pintype "bidirectional"))
    )
    (net (code "71") (name "unconnected-(U1-PA10-Pad43)") (class "Default")
      (node (ref "U1") (pin "43") (pinfunction "PA10_43") (pintype "bidirectional"))
    )
    (net (code "72") (name "unconnected-(U1-PB0-Pad26)") (class "Default")
      (node (ref "U1") (pin "26") (pinfunction "PB0_26") (pintype "bidirectional"))
    )
    (net (code "73") (name "unconnected-(U1-PB1-Pad27)") (class "Default")
      (node (ref "U1") (pin "27") (pinfunction "PB1_27") (pintype "bidirectional"))
    )
    (net (code "74") (name "unconnected-(U1-PB5-Pad57)") (class "Default")
      (node (ref "U1") (pin "57") (pinfunction "PB5_57") (pintype "bidirectional"))
    )
    (net (code "75") (name "unconnected-(U1-PB15-Pad36)") (class "Default")
      (node (ref "U1") (pin "36") (pinfunction "PB15_36") (pintype "bidirectional"))
    )
    (net (code "76") (name "unconnected-(U1-PC0-Pad8)") (class "Default")
      (node (ref "U1") (pin "8") (pinfunction "PC0_8") (pintype "bidirectional"))
    )
    (net (code "77") (name "unconnected-(U1-PC1-Pad9)") (class "Default")
      (node (ref "U1") (pin "9") (pinfunction "PC1_9") (pintype "bidirectional"))
    )
    (net (code "78") (name "unconnected-(U1-PC3-Pad11)") (class "Default")
      (node (ref "U1") (pin "11") (pinfunction "PC3_11") (pintype "bidirectional"))
    )
    (net (code "79") (name "unconnected-(U1-PC6-Pad37)") (class "Default")
      (node (ref "U1") (pin "37") (pinfunction "PC6_37") (pintype "bidirectional"))
    )
    (net (code "80") (name "unconnected-(U1-PC7-Pad38)") (class "Default")
      (node (ref "U1") (pin "38") (pinfunction "PC7_38") (pintype "bidirectional"))
    )
    (net (code "81") (name "unconnected-(U1-PC13-Pad2)") (class "Default")
      (node (ref "U1") (pin "2") (pinfunction "PC13_2") (pintype "bidirectional"))
    )
    (net (code "82") (name "unconnected-(U1-PC14-Pad3)") (class "Default")
      (node (ref "U1") (pin "3") (pinfunction "PC14_3") (pintype "bidirectional"))
    )
    (net (code "83") (name "unconnected-(USB_FS-Pad4)") (class "Default")
      (node (ref "USB_FS") (pin "4") (pinfunction "4_4") (pintype "input"))
    )
  )
)
